# CHIP_tzatziffy_v8.net
KiCad netlist of a schematic drawn in EAGLE
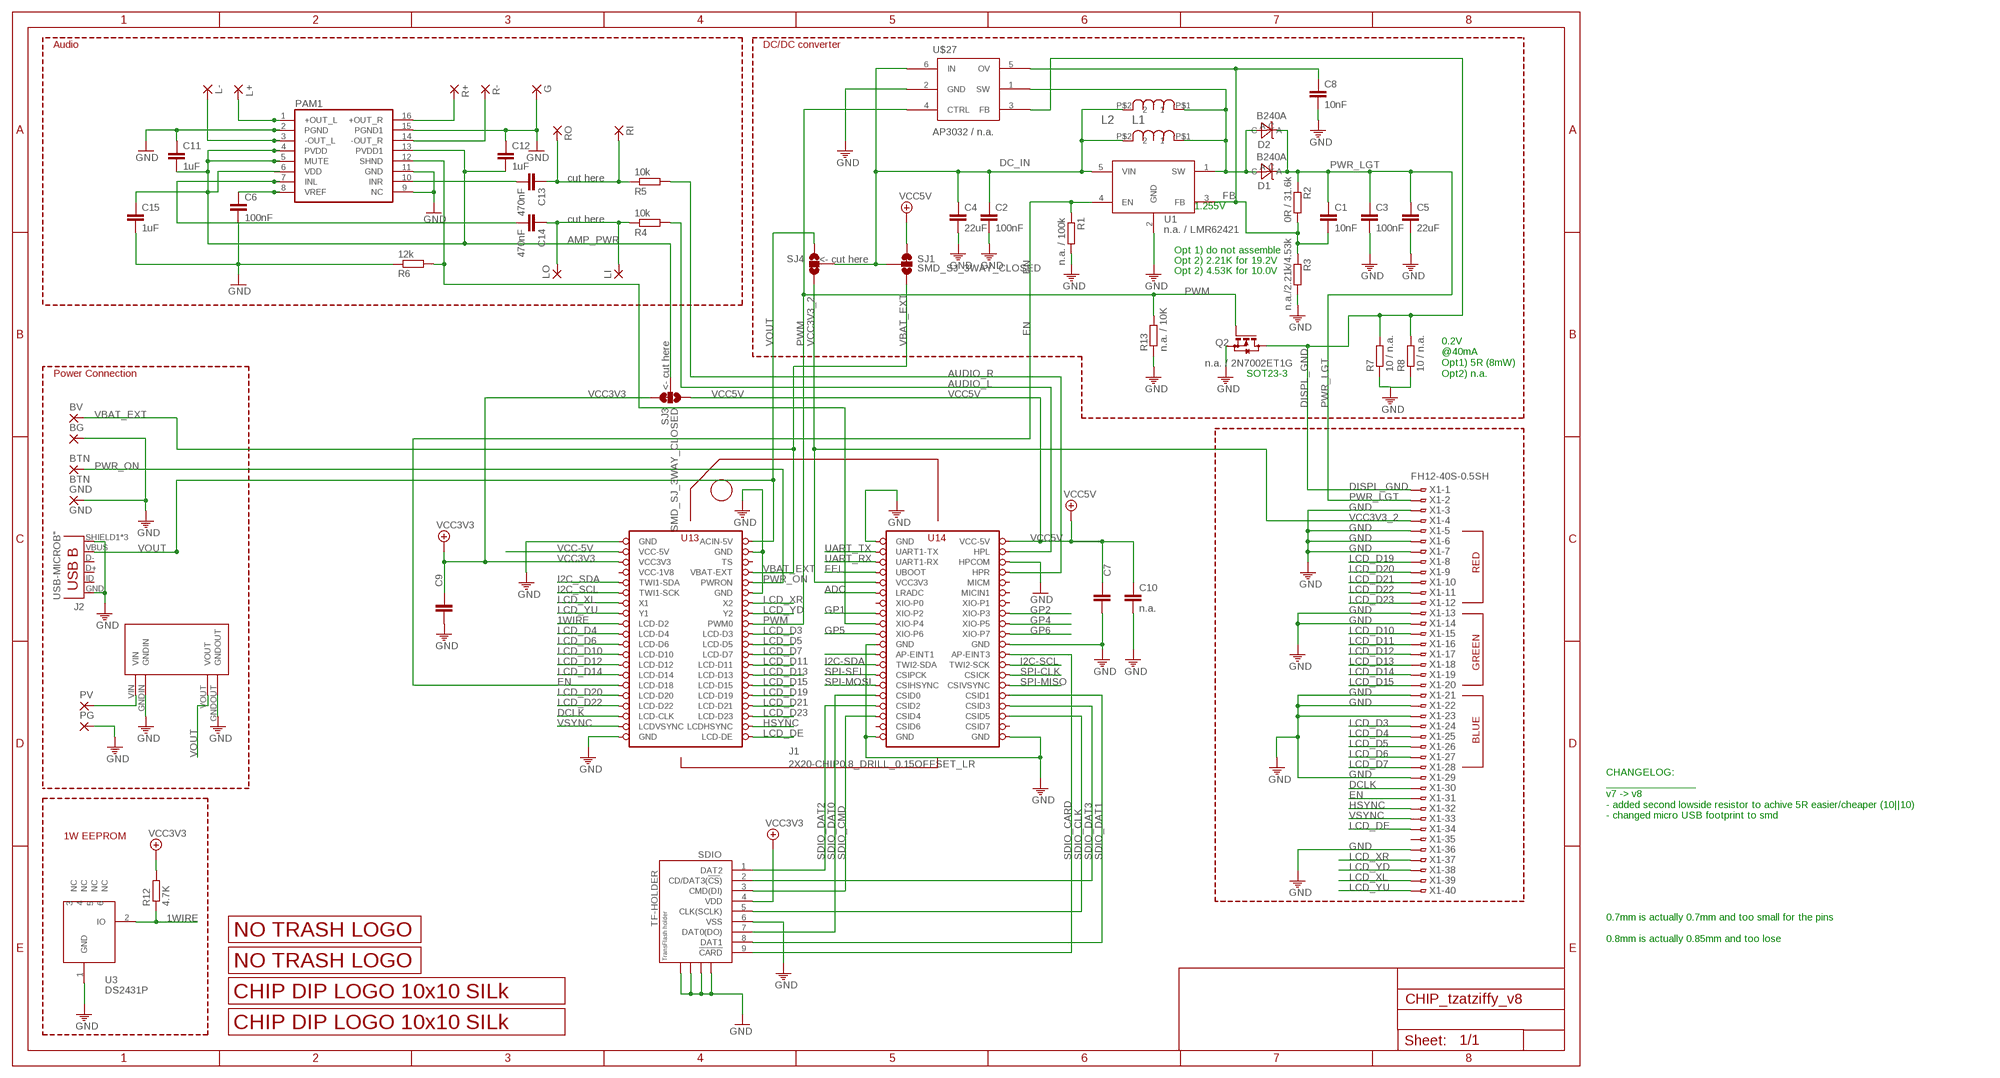
[diagram p0: schematic, sheet 1]

(export (version "E")
  (design (tool "Eeschema 10.0.6"))
  (components
    (comp (ref "BG")
      (value "1,6/0,8")
      (footprint "eagle-import:1,6_0,8")
      (libsource (lib "eagle-import") (part "1,6/0,8"))
    )
    (comp (ref "BTN")
      (value "BTN")
      (footprint "eagle-import:SMD1,27-2,54")
      (libsource (lib "eagle-import") (part "SMD2"))
    )
    (comp (ref "BV")
      (value "1,6/0,8")
      (footprint "eagle-import:1,6_0,8")
      (libsource (lib "eagle-import") (part "1,6/0,8"))
    )
    (comp (ref "C1")
      (value "10nF")
      (footprint "eagle-import:C0805")
      (libsource (lib "eagle-import") (part "C-EUC0805"))
    )
    (comp (ref "C2")
      (value "100nF")
      (footprint "eagle-import:C0805")
      (libsource (lib "eagle-import") (part "C-EUC0805"))
    )
    (comp (ref "C3")
      (value "100nF")
      (footprint "eagle-import:C0805")
      (libsource (lib "eagle-import") (part "C-EUC0805"))
    )
    (comp (ref "C4")
      (value "22uF")
      (footprint "eagle-import:C1206")
      (libsource (lib "eagle-import") (part "C-EUC1206"))
    )
    (comp (ref "C5")
      (value "22uF")
      (footprint "eagle-import:C1206")
      (libsource (lib "eagle-import") (part "C-EUC1206"))
    )
    (comp (ref "C6")
      (value "100nF")
      (footprint "eagle-import:C0805")
      (libsource (lib "eagle-import") (part "C-EUC0805"))
    )
    (comp (ref "C7")
      (value "n.a.")
      (footprint "eagle-import:C0805")
      (libsource (lib "eagle-import") (part "C-EUC0805"))
    )
    (comp (ref "C8")
      (value "10nF")
      (footprint "eagle-import:C0805")
      (libsource (lib "eagle-import") (part "C-EUC0805"))
    )
    (comp (ref "C9")
      (value "n.a.")
      (footprint "eagle-import:C0805")
      (libsource (lib "eagle-import") (part "C-EUC0805"))
    )
    (comp (ref "C10")
      (value "n.a.")
      (footprint "eagle-import:C0805")
      (libsource (lib "eagle-import") (part "C-EUC0805"))
    )
    (comp (ref "C11")
      (value "1uF")
      (footprint "eagle-import:C0805")
      (libsource (lib "eagle-import") (part "C-EUC0805"))
    )
    (comp (ref "C12")
      (value "1uF")
      (footprint "eagle-import:C0805")
      (libsource (lib "eagle-import") (part "C-EUC0805"))
    )
    (comp (ref "C13")
      (value "470nF")
      (footprint "eagle-import:C0805")
      (libsource (lib "eagle-import") (part "C-EUC0805"))
    )
    (comp (ref "C14")
      (value "470nF")
      (footprint "eagle-import:C0805")
      (libsource (lib "eagle-import") (part "C-EUC0805"))
    )
    (comp (ref "C15")
      (value "1uF")
      (footprint "eagle-import:C0805")
      (libsource (lib "eagle-import") (part "C-EUC0805"))
    )
    (comp (ref "D1")
      (value "B240A")
      (footprint "eagle-import:DO-214AC")
      (fields (field (name "MFG") "DIGIKEY") (field (name "VENDOR_PART_NUMBER") "B240A-13-F"))
      (libsource (lib "eagle-import") (part "DIODE_SCHTKY_B240"))
    )
    (comp (ref "D2")
      (value "B240A")
      (footprint "eagle-import:DO-214AC")
      (fields (field (name "MFG") "DIGIKEY") (field (name "VENDOR_PART_NUMBER") "B240A-13-F"))
      (libsource (lib "eagle-import") (part "DIODE_SCHTKY_B240"))
    )
    (comp (ref "G")
      (value "1,6/0,8")
      (footprint "eagle-import:1,6_0,8")
      (libsource (lib "eagle-import") (part "1,6/0,8"))
    )
    (comp (ref "GND")
      (value "GND")
      (footprint "eagle-import:SMD1,27-2,54")
      (libsource (lib "eagle-import") (part "SMD2"))
    )
    (comp (ref "J1")
      (value "2X20-CHIP0.8_DRILL_0.15OFFSET_LR")
      (footprint "eagle-import:2X20CHIP_0.15MM_OFFSET_TH_08")
      (libsource (lib "eagle-import") (part "2X20-CHIP0.8_DRILL_0.15OFFSET_LR"))
    )
    (comp (ref "J2")
      (value "USB-MICROB\"")
      (footprint "eagle-import:USB-B-MICRO-SMD_V03")
      (libsource (lib "eagle-import") (part "USB-MICROB{dblquote}"))
    )
    (comp (ref "L+")
      (value "1,6/0,8")
      (footprint "eagle-import:1,6_0,8")
      (libsource (lib "eagle-import") (part "1,6/0,8"))
    )
    (comp (ref "L-")
      (value "1,6/0,8")
      (footprint "eagle-import:1,6_0,8")
      (libsource (lib "eagle-import") (part "1,6/0,8"))
    )
    (comp (ref "L1")
      (value "SRN6045-100M")
      (footprint "eagle-import:SRN6045")
      (fields (field (name "MFG") "DIGIKEY"))
      (libsource (lib "eagle-import") (part "SRN6045-100M"))
    )
    (comp (ref "L2")
      (value "SRN6045-100M")
      (footprint "eagle-import:SRN6045")
      (fields (field (name "MFG") "DIGIKEY"))
      (libsource (lib "eagle-import") (part "SRN6045-100M"))
    )
    (comp (ref "LI")
      (value "1,6/0,8")
      (footprint "eagle-import:1,6_0,8")
      (libsource (lib "eagle-import") (part "1,6/0,8"))
    )
    (comp (ref "LO")
      (value "1,6/0,8")
      (footprint "eagle-import:1,6_0,8")
      (libsource (lib "eagle-import") (part "1,6/0,8"))
    )
    (comp (ref "PAM1")
      (value "PAM8403")
      (footprint "eagle-import:SOP-16")
      (libsource (lib "eagle-import") (part "PAM8403"))
    )
    (comp (ref "PG")
      (value "1,6/0,8")
      (footprint "eagle-import:1,6_0,8")
      (libsource (lib "eagle-import") (part "1,6/0,8"))
    )
    (comp (ref "PV")
      (value "1,6/0,8")
      (footprint "eagle-import:1,6_0,8")
      (libsource (lib "eagle-import") (part "1,6/0,8"))
    )
    (comp (ref "Q2")
      (value "n.a. / 2N7002ET1G")
      (footprint "eagle-import:SOT23")
      (libsource (lib "eagle-import") (part "BSS123"))
    )
    (comp (ref "R+")
      (value "1,6/0,8")
      (footprint "eagle-import:1,6_0,8")
      (libsource (lib "eagle-import") (part "1,6/0,8"))
    )
    (comp (ref "R-")
      (value "1,6/0,8")
      (footprint "eagle-import:1,6_0,8")
      (libsource (lib "eagle-import") (part "1,6/0,8"))
    )
    (comp (ref "R1")
      (value "n.a. / 100k")
      (footprint "eagle-import:M0805")
      (libsource (lib "eagle-import") (part "R-EU_M0805"))
    )
    (comp (ref "R2")
      (value "0R / 31.6k")
      (footprint "eagle-import:M0805")
      (libsource (lib "eagle-import") (part "R-EU_M0805"))
    )
    (comp (ref "R3")
      (value "n.a./2.21k/4.53k")
      (footprint "eagle-import:M0805")
      (libsource (lib "eagle-import") (part "R-EU_M0805"))
    )
    (comp (ref "R4")
      (value "10k")
      (footprint "eagle-import:R0805")
      (libsource (lib "eagle-import") (part "R-EU_R0805"))
    )
    (comp (ref "R5")
      (value "10k")
      (footprint "eagle-import:R0805")
      (libsource (lib "eagle-import") (part "R-EU_R0805"))
    )
    (comp (ref "R6")
      (value "12k")
      (footprint "eagle-import:R0805")
      (libsource (lib "eagle-import") (part "R-EU_R0805"))
    )
    (comp (ref "R7")
      (value "10 / n.a.")
      (footprint "eagle-import:M0805")
      (libsource (lib "eagle-import") (part "R-EU_M0805"))
    )
    (comp (ref "R8")
      (value "10 / n.a.")
      (footprint "eagle-import:M0805")
      (libsource (lib "eagle-import") (part "R-EU_M0805"))
    )
    (comp (ref "R12")
      (value "4.7K")
      (footprint "eagle-import:M0805")
      (libsource (lib "eagle-import") (part "R-EU_M0805"))
    )
    (comp (ref "R13")
      (value "n.a. / 10K")
      (footprint "eagle-import:M0805")
      (libsource (lib "eagle-import") (part "R-EU_M0805"))
    )
    (comp (ref "RI")
      (value "1,6/0,8")
      (footprint "eagle-import:1,6_0,8")
      (libsource (lib "eagle-import") (part "1,6/0,8"))
    )
    (comp (ref "RO")
      (value "1,6/0,8")
      (footprint "eagle-import:1,6_0,8")
      (libsource (lib "eagle-import") (part "1,6/0,8"))
    )
    (comp (ref "SDIO")
      (value "TF-HOLDER")
      (footprint "eagle-import:TF-PULL")
      (libsource (lib "eagle-import") (part "TF-HOLDER"))
    )
    (comp (ref "SJ1")
      (value "SMD_SJ_3WAY_CLOSED")
      (footprint "eagle-import:SMD_SJ_3WAY_CLOSED")
      (libsource (lib "eagle-import") (part "SMD_SJ_3WAY_CLOSED"))
    )
    (comp (ref "SJ3")
      (value "SMD_SJ_3WAY_CLOSED")
      (footprint "eagle-import:SMD_SJ_3WAY_CLOSED")
      (libsource (lib "eagle-import") (part "SMD_SJ_3WAY_CLOSED"))
    )
    (comp (ref "SJ4")
      (value "SMD_SJ_3WAY_OPENT")
      (footprint "eagle-import:SMD_SJ_3WAY_OPEN")
      (libsource (lib "eagle-import") (part "SMD_SJ_3WAY_OPENT"))
    )
    (comp (ref "U$2")
      (value "LOGO_10X10_SILK")
      (footprint "eagle-import:LOGO2_10X10_SILK")
      (libsource (lib "eagle-import") (part "LOGO_10X10_SILK"))
    )
    (comp (ref "U$3")
      (value "LOGO_NO_TRASHROHS")
      (footprint "eagle-import:LOGO_ROHS_SYM")
      (libsource (lib "eagle-import") (part "LOGO_NO_TRASHROHS"))
    )
    (comp (ref "U$4")
      (value "LOGO_NO_TRASHNO_TRASH")
      (footprint "eagle-import:LOGO_ROHS_NO_TRASH")
      (libsource (lib "eagle-import") (part "LOGO_NO_TRASHNO_TRASH"))
    )
    (comp (ref "U$5")
      (value "LOGO_10X10_SILK")
      (footprint "eagle-import:LOGO2_10X10_SILK")
      (libsource (lib "eagle-import") (part "LOGO_10X10_SILK"))
    )
    (comp (ref "U$10")
      (value "MP1584EN_FRAMELESS")
      (footprint "eagle-import:MP1584EN_FRAMELESS")
      (libsource (lib "eagle-import") (part "MP1584EN_FRAMELESS"))
    )
    (comp (ref "U$27")
      (value "AP3032 / n.a.")
      (footprint "eagle-import:SOT23-6")
      (libsource (lib "eagle-import") (part "AP3032"))
    )
    (comp (ref "U1")
      (value "n.a. / LMR62421")
      (footprint "eagle-import:SOT23-5")
      (fields (field (name "MFG") "DIGIKEY") (field (name "VENDOR_PART_NUMBER") "LMR62421XMFE/NOPB"))
      (libsource (lib "eagle-import") (part "LMR62421"))
    )
    (comp (ref "U3")
      (value "DS2431P")
      (footprint "eagle-import:TSOC6")
      (fields (field (name "MFG") "DIGIKEY") (field (name "VENDOR_PART_NUMBER") "DS2431P+T&R"))
      (libsource (lib "eagle-import") (part "DS2431P"))
    )
    (comp (ref "X1")
      (value "FH12-40S-0.5SH")
      (footprint "eagle-import:FH12-40S-0.5SH")
      (fields (field (name "MFG") "DIGIKEY") (field (name "VENDOR_PART_NUMBER") "FH12-40S-0.5SH(55)"))
      (libsource (lib "eagle-import") (part "FH12-40S-0.5SH"))
    )
  )
  (nets
    (net (code "1") (name "/1WIRE") (class "Default")
      (node (ref "J1") (pin "LCD-D2") (pinfunction "LCD-D2_LCD-D2") (pintype "passive"))
      (node (ref "R12") (pin "1") (pinfunction "1_1") (pintype "passive"))
      (node (ref "U3") (pin "2") (pinfunction "IO_2") (pintype "bidirectional"))
    )
    (net (code "2") (name "/ADC") (class "Default")
      (node (ref "J1") (pin "LRADC") (pinfunction "LRADC_LRADC") (pintype "passive"))
    )
    (net (code "3") (name "/AMP_PWR") (class "Default")
      (node (ref "C11") (pin "2") (pinfunction "2_2") (pintype "passive"))
      (node (ref "C12") (pin "2") (pinfunction "2_2") (pintype "passive"))
      (node (ref "C15") (pin "1") (pinfunction "1_1") (pintype "passive"))
      (node (ref "PAM1") (pin "13") (pinfunction "PVDD1_13") (pintype "output"))
      (node (ref "PAM1") (pin "4") (pinfunction "PVDD_4") (pintype "input"))
      (node (ref "PAM1") (pin "5") (pinfunction "MUTE_5") (pintype "input"))
      (node (ref "PAM1") (pin "6") (pinfunction "VDD_6") (pintype "input"))
      (node (ref "SJ3") (pin "2") (pinfunction "2_2") (pintype "passive"))
    )
    (net (code "4") (name "/AUDIO_L") (class "Default")
      (node (ref "J1") (pin "HPL") (pinfunction "HPL_HPL") (pintype "passive"))
      (node (ref "R4") (pin "2") (pinfunction "2_2") (pintype "passive"))
    )
    (net (code "5") (name "/AUDIO_R") (class "Default")
      (node (ref "J1") (pin "HPR") (pinfunction "HPR_HPR") (pintype "passive"))
      (node (ref "R5") (pin "2") (pinfunction "2_2") (pintype "passive"))
    )
    (net (code "6") (name "/DCLK") (class "Default")
      (node (ref "J1") (pin "LCD-CLK") (pinfunction "LCD-CLK_LCD-CLK") (pintype "passive"))
      (node (ref "X1") (pin "30") (pinfunction "1_30") (pintype "passive"))
    )
    (net (code "7") (name "/DC_IN") (class "Default")
      (node (ref "C2") (pin "1") (pinfunction "1_1") (pintype "passive"))
      (node (ref "C4") (pin "1") (pinfunction "1_1") (pintype "passive"))
      (node (ref "L1") (pin "P$2") (pinfunction "2_P$2") (pintype "passive"))
      (node (ref "L2") (pin "P$2") (pinfunction "2_P$2") (pintype "passive"))
      (node (ref "SJ1") (pin "2") (pinfunction "2_2") (pintype "passive"))
      (node (ref "SJ4") (pin "2") (pinfunction "2_2") (pintype "passive"))
      (node (ref "U$27") (pin "6") (pinfunction "IN_6") (pintype "power_in"))
      (node (ref "U1") (pin "5") (pinfunction "VIN_5") (pintype "bidirectional"))
    )
    (net (code "8") (name "/DISPL_GND") (class "Default")
      (node (ref "Q2") (pin "3") (pinfunction "D_3") (pintype "passive"))
      (node (ref "R7") (pin "2") (pinfunction "2_2") (pintype "passive"))
      (node (ref "R8") (pin "2") (pinfunction "2_2") (pintype "passive"))
      (node (ref "U$27") (pin "3") (pinfunction "FB_3") (pintype "passive"))
      (node (ref "X1") (pin "1") (pinfunction "1_1") (pintype "passive"))
    )
    (net (code "9") (name "/EN") (class "Default")
      (node (ref "J1") (pin "LCD-D18") (pinfunction "LCD-D18_LCD-D18") (pintype "passive"))
      (node (ref "R1") (pin "1") (pinfunction "1_1") (pintype "passive"))
      (node (ref "U1") (pin "4") (pinfunction "EN_4") (pintype "bidirectional"))
      (node (ref "X1") (pin "31") (pinfunction "1_31") (pintype "passive"))
    )
    (net (code "10") (name "/FB") (class "Default")
      (node (ref "C1") (pin "2") (pinfunction "2_2") (pintype "passive"))
      (node (ref "C8") (pin "1") (pinfunction "1_1") (pintype "passive"))
      (node (ref "R2") (pin "2") (pinfunction "2_2") (pintype "passive"))
      (node (ref "R3") (pin "1") (pinfunction "1_1") (pintype "passive"))
      (node (ref "U$27") (pin "5") (pinfunction "OV_5") (pintype "power_in"))
      (node (ref "U1") (pin "3") (pinfunction "FB_3") (pintype "bidirectional"))
    )
    (net (code "11") (name "/FEL") (class "Default")
      (node (ref "J1") (pin "FEL") (pinfunction "UBOOT_FEL") (pintype "passive"))
    )
    (net (code "12") (name "/GP1") (class "Default")
      (node (ref "J1") (pin "XIO-P2") (pinfunction "XIO-P2_XIO-P2") (pintype "passive"))
    )
    (net (code "13") (name "/GP2") (class "Default")
      (node (ref "J1") (pin "XIO-P3") (pinfunction "XIO-P3_XIO-P3") (pintype "passive"))
    )
    (net (code "14") (name "/GP4") (class "Default")
      (node (ref "J1") (pin "XIO-P5") (pinfunction "XIO-P5_XIO-P5") (pintype "passive"))
    )
    (net (code "15") (name "/GP5") (class "Default")
      (node (ref "J1") (pin "XIO-P6") (pinfunction "XIO-P6_XIO-P6") (pintype "passive"))
    )
    (net (code "16") (name "/GP6") (class "Default")
      (node (ref "J1") (pin "XIO-P7") (pinfunction "XIO-P7_XIO-P7") (pintype "passive"))
    )
    (net (code "17") (name "/HSYNC") (class "Default")
      (node (ref "J1") (pin "LCD-HSYNC") (pinfunction "LCDHSYNC_LCD-HSYNC") (pintype "passive"))
      (node (ref "X1") (pin "32") (pinfunction "1_32") (pintype "passive"))
    )
    (net (code "18") (name "/I2C-SCL") (class "Default")
      (node (ref "J1") (pin "TWI2-SCK") (pinfunction "TWI2-SCK_TWI2-SCK") (pintype "passive"))
    )
    (net (code "19") (name "/I2C-SDA") (class "Default")
      (node (ref "J1") (pin "TWI2-SDA") (pinfunction "TWI2-SDA_TWI2-SDA") (pintype "passive"))
    )
    (net (code "20") (name "/I2C_SCL") (class "Default")
      (node (ref "J1") (pin "TWI1-SCK") (pinfunction "TWI1-SCK_TWI1-SCK") (pintype "passive"))
    )
    (net (code "21") (name "/I2C_SDA") (class "Default")
      (node (ref "J1") (pin "TWI1-SDA") (pinfunction "TWI1-SDA_TWI1-SDA") (pintype "passive"))
    )
    (net (code "22") (name "/LCD_D3") (class "Default")
      (node (ref "J1") (pin "LCD-D3") (pinfunction "LCD-D3_LCD-D3") (pintype "passive"))
      (node (ref "X1") (pin "24") (pinfunction "1_24") (pintype "passive"))
    )
    (net (code "23") (name "/LCD_D4") (class "Default")
      (node (ref "J1") (pin "LCD-D4") (pinfunction "LCD-D4_LCD-D4") (pintype "passive"))
      (node (ref "X1") (pin "25") (pinfunction "1_25") (pintype "passive"))
    )
    (net (code "24") (name "/LCD_D5") (class "Default")
      (node (ref "J1") (pin "LCD-D5") (pinfunction "LCD-D5_LCD-D5") (pintype "passive"))
      (node (ref "X1") (pin "26") (pinfunction "1_26") (pintype "passive"))
    )
    (net (code "25") (name "/LCD_D6") (class "Default")
      (node (ref "J1") (pin "LCD-D6") (pinfunction "LCD-D6_LCD-D6") (pintype "passive"))
      (node (ref "X1") (pin "27") (pinfunction "1_27") (pintype "passive"))
    )
    (net (code "26") (name "/LCD_D7") (class "Default")
      (node (ref "J1") (pin "LCD-D7") (pinfunction "LCD-D7_LCD-D7") (pintype "passive"))
      (node (ref "X1") (pin "28") (pinfunction "1_28") (pintype "passive"))
    )
    (net (code "27") (name "/LCD_D10") (class "Default")
      (node (ref "J1") (pin "LCD-D10") (pinfunction "LCD-D10_LCD-D10") (pintype "passive"))
      (node (ref "X1") (pin "15") (pinfunction "1_15") (pintype "passive"))
    )
    (net (code "28") (name "/LCD_D11") (class "Default")
      (node (ref "J1") (pin "LCD-D11") (pinfunction "LCD-D11_LCD-D11") (pintype "passive"))
      (node (ref "X1") (pin "16") (pinfunction "1_16") (pintype "passive"))
    )
    (net (code "29") (name "/LCD_D12") (class "Default")
      (node (ref "J1") (pin "LCD-D12") (pinfunction "LCD-D12_LCD-D12") (pintype "passive"))
      (node (ref "X1") (pin "17") (pinfunction "1_17") (pintype "passive"))
    )
    (net (code "30") (name "/LCD_D13") (class "Default")
      (node (ref "J1") (pin "LCD-D13") (pinfunction "LCD-D13_LCD-D13") (pintype "passive"))
      (node (ref "X1") (pin "18") (pinfunction "1_18") (pintype "passive"))
    )
    (net (code "31") (name "/LCD_D14") (class "Default")
      (node (ref "J1") (pin "LCD-D14") (pinfunction "LCD-D14_LCD-D14") (pintype "passive"))
      (node (ref "X1") (pin "19") (pinfunction "1_19") (pintype "passive"))
    )
    (net (code "32") (name "/LCD_D15") (class "Default")
      (node (ref "J1") (pin "LCD-D15") (pinfunction "LCD-D15_LCD-D15") (pintype "passive"))
      (node (ref "X1") (pin "20") (pinfunction "1_20") (pintype "passive"))
    )
    (net (code "33") (name "/LCD_D19") (class "Default")
      (node (ref "J1") (pin "LCD-D19") (pinfunction "LCD-D19_LCD-D19") (pintype "passive"))
      (node (ref "X1") (pin "8") (pinfunction "1_8") (pintype "passive"))
    )
    (net (code "34") (name "/LCD_D20") (class "Default")
      (node (ref "J1") (pin "LCD-D20") (pinfunction "LCD-D20_LCD-D20") (pintype "passive"))
      (node (ref "X1") (pin "9") (pinfunction "1_9") (pintype "passive"))
    )
    (net (code "35") (name "/LCD_D21") (class "Default")
      (node (ref "J1") (pin "LCD-D21") (pinfunction "LCD-D21_LCD-D21") (pintype "passive"))
      (node (ref "X1") (pin "10") (pinfunction "1_10") (pintype "passive"))
    )
    (net (code "36") (name "/LCD_D22") (class "Default")
      (node (ref "J1") (pin "LCD-D22") (pinfunction "LCD-D22_LCD-D22") (pintype "passive"))
      (node (ref "X1") (pin "11") (pinfunction "1_11") (pintype "passive"))
    )
    (net (code "37") (name "/LCD_D23") (class "Default")
      (node (ref "J1") (pin "LCD-D23") (pinfunction "LCD-D23_LCD-D23") (pintype "passive"))
      (node (ref "X1") (pin "12") (pinfunction "1_12") (pintype "passive"))
    )
    (net (code "38") (name "/LCD_DE") (class "Default")
      (node (ref "J1") (pin "LCD-DE") (pinfunction "LCD-DE_LCD-DE") (pintype "passive"))
      (node (ref "X1") (pin "34") (pinfunction "1_34") (pintype "passive"))
    )
    (net (code "39") (name "/LCD_XL") (class "Default")
      (node (ref "J1") (pin "X1") (pinfunction "X1_X1") (pintype "passive"))
      (node (ref "X1") (pin "39") (pinfunction "1_39") (pintype "passive"))
    )
    (net (code "40") (name "/LCD_XR") (class "Default")
      (node (ref "J1") (pin "X2") (pinfunction "X2_X2") (pintype "passive"))
      (node (ref "X1") (pin "37") (pinfunction "1_37") (pintype "passive"))
    )
    (net (code "41") (name "/LCD_YD") (class "Default")
      (node (ref "J1") (pin "Y2") (pinfunction "Y2_Y2") (pintype "passive"))
      (node (ref "X1") (pin "38") (pinfunction "1_38") (pintype "passive"))
    )
    (net (code "42") (name "/LCD_YU") (class "Default")
      (node (ref "J1") (pin "Y1") (pinfunction "Y1_Y1") (pintype "passive"))
      (node (ref "X1") (pin "40") (pinfunction "1_40") (pintype "passive"))
    )
    (net (code "43") (name "/PWM") (class "Default")
      (node (ref "J1") (pin "PWM0") (pinfunction "PWM0_PWM0") (pintype "passive"))
      (node (ref "Q2") (pin "1") (pinfunction "G_1") (pintype "passive"))
      (node (ref "R13") (pin "2") (pinfunction "2_2") (pintype "passive"))
      (node (ref "U$27") (pin "4") (pinfunction "CTRL_4") (pintype "input"))
    )
    (net (code "44") (name "/PWR_LGT") (class "Default")
      (node (ref "C1") (pin "1") (pinfunction "1_1") (pintype "passive"))
      (node (ref "C3") (pin "1") (pinfunction "1_1") (pintype "passive"))
      (node (ref "C5") (pin "1") (pinfunction "1_1") (pintype "passive"))
      (node (ref "D1") (pin "C") (pinfunction "C_C") (pintype "bidirectional"))
      (node (ref "D2") (pin "C") (pinfunction "C_C") (pintype "bidirectional"))
      (node (ref "R2") (pin "1") (pinfunction "1_1") (pintype "passive"))
      (node (ref "X1") (pin "2") (pinfunction "1_2") (pintype "passive"))
    )
    (net (code "45") (name "/PWR_ON") (class "Default")
      (node (ref "BTN") (pin "1") (pinfunction "P_1") (pintype "passive"))
      (node (ref "J1") (pin "PWRON") (pinfunction "PWRON_PWRON") (pintype "passive"))
    )
    (net (code "46") (name "/SDIO_CARD") (class "Default")
      (node (ref "J1") (pin "AP-EINT3") (pinfunction "AP-EINT3_AP-EINT3") (pintype "passive"))
      (node (ref "SDIO") (pin "9") (pinfunction "~{CARD}_9") (pintype "passive"))
    )
    (net (code "47") (name "/SDIO_CLK") (class "Default")
      (node (ref "J1") (pin "CSID5") (pinfunction "CSID5_CSID5") (pintype "passive"))
      (node (ref "SDIO") (pin "5") (pinfunction "CLK(SCLK)_5") (pintype "input"))
    )
    (net (code "48") (name "/SDIO_CMD") (class "Default")
      (node (ref "J1") (pin "CSID4") (pinfunction "CSID4_CSID4") (pintype "passive"))
      (node (ref "SDIO") (pin "3") (pinfunction "CMD(DI)_3") (pintype "bidirectional"))
    )
    (net (code "49") (name "/SDIO_DAT0") (class "Default")
      (node (ref "J1") (pin "CSID0") (pinfunction "CSID0_CSID0") (pintype "passive"))
      (node (ref "SDIO") (pin "7") (pinfunction "DAT0(DO)_7") (pintype "bidirectional"))
    )
    (net (code "50") (name "/SDIO_DAT1") (class "Default")
      (node (ref "J1") (pin "CSID1") (pinfunction "CSID1_CSID1") (pintype "passive"))
      (node (ref "SDIO") (pin "8") (pinfunction "DAT1_8") (pintype "bidirectional"))
    )
    (net (code "51") (name "/SDIO_DAT2") (class "Default")
      (node (ref "J1") (pin "CSID2") (pinfunction "CSID2_CSID2") (pintype "passive"))
      (node (ref "SDIO") (pin "1") (pinfunction "DAT2_1") (pintype "bidirectional"))
    )
    (net (code "52") (name "/SDIO_DAT3") (class "Default")
      (node (ref "J1") (pin "CSID3") (pinfunction "CSID3_CSID3") (pintype "passive"))
      (node (ref "SDIO") (pin "2") (pinfunction "CD/DAT3(~{CS})_2") (pintype "bidirectional"))
    )
    (net (code "53") (name "/SPI-CLK") (class "Default")
      (node (ref "J1") (pin "CSICK") (pinfunction "CSICK_CSICK") (pintype "passive"))
    )
    (net (code "54") (name "/SPI-MISO") (class "Default")
      (node (ref "J1") (pin "CSIVSYNC") (pinfunction "CSIVSYNC_CSIVSYNC") (pintype "passive"))
    )
    (net (code "55") (name "/SPI-MOSI") (class "Default")
      (node (ref "J1") (pin "CSIHSYNC") (pinfunction "CSIHSYNC_CSIHSYNC") (pintype "passive"))
    )
    (net (code "56") (name "/SPI-SEL") (class "Default")
      (node (ref "J1") (pin "CSIPCK") (pinfunction "CSIPCK_CSIPCK") (pintype "passive"))
    )
    (net (code "57") (name "/UART_RX") (class "Default")
      (node (ref "J1") (pin "UART1-RX") (pinfunction "UART1-RX_UART1-RX") (pintype "passive"))
    )
    (net (code "58") (name "/UART_TX") (class "Default")
      (node (ref "J1") (pin "UART1-TX") (pinfunction "UART1-TX_UART1-TX") (pintype "passive"))
    )
    (net (code "59") (name "/VBAT_EXT") (class "Default")
      (node (ref "BV") (pin "1") (pinfunction "P_1") (pintype "passive"))
      (node (ref "J1") (pin "BAT") (pinfunction "VBAT-EXT_BAT") (pintype "passive"))
      (node (ref "SJ1") (pin "3") (pinfunction "3_3") (pintype "passive"))
    )
    (net (code "60") (name "/VCC-1V8") (class "Default")
      (node (ref "J1") (pin "VCC1V8") (pinfunction "VCC-1V8_VCC1V8") (pintype "power_in"))
    )
    (net (code "61") (name "/VCC-5V") (class "Default")
      (node (ref "J1") (pin "VCC5V@0") (pinfunction "VCC-5V_VCC5V@0") (pintype "power_in"))
    )
    (net (code "62") (name "/VCC3V3_2") (class "Default")
      (node (ref "J1") (pin "VCC3V3@1") (pinfunction "VCC3V3_VCC3V3@1") (pintype "power_in"))
      (node (ref "SJ4") (pin "3") (pinfunction "3_3") (pintype "passive"))
      (node (ref "X1") (pin "4") (pinfunction "1_4") (pintype "passive"))
    )
    (net (code "63") (name "/VOUT") (class "Default")
      (node (ref "J1") (pin "CHG-IN") (pinfunction "ACIN-5V_CHG-IN") (pintype "passive"))
      (node (ref "J2") (pin "VBUS") (pinfunction "VBUS_VBUS") (pintype "bidirectional"))
      (node (ref "SJ4") (pin "1") (pinfunction "1_1") (pintype "passive"))
      (node (ref "U$10") (pin "VOUT") (pinfunction "VOUT_VOUT") (pintype "power_in"))
    )
    (net (code "64") (name "/VSYNC") (class "Default")
      (node (ref "J1") (pin "LCD-VSYNC") (pinfunction "LCDVSYNC_LCD-VSYNC") (pintype "passive"))
      (node (ref "X1") (pin "33") (pinfunction "1_33") (pintype "passive"))
    )
    (net (code "65") (name "GND") (class "Default")
      (node (ref "BG") (pin "1") (pinfunction "P_1") (pintype "passive"))
      (node (ref "C10") (pin "2") (pinfunction "2_2") (pintype "passive"))
      (node (ref "C11") (pin "1") (pinfunction "1_1") (pintype "passive"))
      (node (ref "C12") (pin "1") (pinfunction "1_1") (pintype "passive"))
      (node (ref "C15") (pin "2") (pinfunction "2_2") (pintype "passive"))
      (node (ref "C2") (pin "2") (pinfunction "2_2") (pintype "passive"))
      (node (ref "C3") (pin "2") (pinfunction "2_2") (pintype "passive"))
      (node (ref "C4") (pin "2") (pinfunction "2_2") (pintype "passive"))
      (node (ref "C5") (pin "2") (pinfunction "2_2") (pintype "passive"))
      (node (ref "C6") (pin "2") (pinfunction "2_2") (pintype "passive"))
      (node (ref "C7") (pin "2") (pinfunction "2_2") (pintype "passive"))
      (node (ref "C8") (pin "2") (pinfunction "2_2") (pintype "passive"))
      (node (ref "C9") (pin "2") (pinfunction "2_2") (pintype "passive"))
      (node (ref "G") (pin "1") (pinfunction "P_1") (pintype "passive"))
      (node (ref "GND") (pin "1") (pinfunction "P_1") (pintype "passive"))
      (node (ref "J1") (pin "GND@1") (pinfunction "GND_GND@1") (pintype "power_in"))
      (node (ref "J1") (pin "GND@10") (pinfunction "GND_GND@10") (pintype "power_in"))
      (node (ref "J1") (pin "GND@2") (pinfunction "GND_GND@2") (pintype "power_in"))
      (node (ref "J1") (pin "GND@3") (pinfunction "GND_GND@3") (pintype "power_in"))
      (node (ref "J1") (pin "GND@4") (pinfunction "GND_GND@4") (pintype "power_in"))
      (node (ref "J1") (pin "GND@5") (pinfunction "GND_GND@5") (pintype "power_in"))
      (node (ref "J1") (pin "GND@6") (pinfunction "GND_GND@6") (pintype "power_in"))
      (node (ref "J1") (pin "GND@7") (pinfunction "GND_GND@7") (pintype "power_in"))
      (node (ref "J1") (pin "GND@8") (pinfunction "GND_GND@8") (pintype "power_in"))
      (node (ref "J1") (pin "HPCOM") (pinfunction "HPCOM_HPCOM") (pintype "passive"))
      (node (ref "J2") (pin "GND") (pinfunction "GND_GND") (pintype "bidirectional"))
      (node (ref "J2") (pin "SHIELD1") (pinfunction "SHIELD_SHIELD1") (pintype "bidirectional"))
      (node (ref "J2") (pin "SHIELD2") (pinfunction "SHIELD_SHIELD2") (pintype "bidirectional"))
      (node (ref "J2") (pin "SHIELD3") (pinfunction "SHIELD_SHIELD3") (pintype "bidirectional"))
      (node (ref "PAM1") (pin "11") (pinfunction "GND_11") (pintype "output"))
      (node (ref "PAM1") (pin "15") (pinfunction "PGND1_15") (pintype "output"))
      (node (ref "PAM1") (pin "2") (pinfunction "PGND_2") (pintype "input"))
      (node (ref "PAM1") (pin "9") (pinfunction "NC_9") (pintype "output"))
      (node (ref "PG") (pin "1") (pinfunction "P_1") (pintype "passive"))
      (node (ref "Q2") (pin "2") (pinfunction "S_2") (pintype "passive"))
      (node (ref "R1") (pin "2") (pinfunction "2_2") (pintype "passive"))
      (node (ref "R13") (pin "1") (pinfunction "1_1") (pintype "passive"))
      (node (ref "R3") (pin "2") (pinfunction "2_2") (pintype "passive"))
      (node (ref "R6") (pin "1") (pinfunction "1_1") (pintype "passive"))
      (node (ref "R7") (pin "1") (pinfunction "1_1") (pintype "passive"))
      (node (ref "R8") (pin "1") (pinfunction "1_1") (pintype "passive"))
      (node (ref "SDIO") (pin "6") (pinfunction "VSS_6") (pintype "power_in"))
      (node (ref "SDIO") (pin "S1") (pinfunction "S1_S1") (pintype "passive"))
      (node (ref "SDIO") (pin "S2") (pinfunction "S2_S2") (pintype "passive"))
      (node (ref "SDIO") (pin "S3") (pinfunction "S3_S3") (pintype "passive"))
      (node (ref "SDIO") (pin "S4") (pinfunction "S4_S4") (pintype "passive"))
      (node (ref "U$10") (pin "GNDIN") (pinfunction "GNDIN_GNDIN") (pintype "power_in"))
      (node (ref "U$10") (pin "GNDOUT") (pinfunction "GNDOUT_GNDOUT") (pintype "power_in"))
      (node (ref "U$27") (pin "2") (pinfunction "GND_2") (pintype "power_in"))
      (node (ref "U1") (pin "2") (pinfunction "GND_2") (pintype "bidirectional"))
      (node (ref "U3") (pin "1") (pinfunction "GND_1") (pintype "bidirectional"))
      (node (ref "X1") (pin "13") (pinfunction "1_13") (pintype "passive"))
      (node (ref "X1") (pin "14") (pinfunction "1_14") (pintype "passive"))
      (node (ref "X1") (pin "21") (pinfunction "1_21") (pintype "passive"))
      (node (ref "X1") (pin "22") (pinfunction "1_22") (pintype "passive"))
      (node (ref "X1") (pin "23") (pinfunction "1_23") (pintype "passive"))
      (node (ref "X1") (pin "29") (pinfunction "1_29") (pintype "passive"))
      (node (ref "X1") (pin "3") (pinfunction "1_3") (pintype "passive"))
      (node (ref "X1") (pin "36") (pinfunction "1_36") (pintype "passive"))
      (node (ref "X1") (pin "5") (pinfunction "1_5") (pintype "passive"))
      (node (ref "X1") (pin "6") (pinfunction "1_6") (pintype "passive"))
      (node (ref "X1") (pin "7") (pinfunction "1_7") (pintype "passive"))
    )
    (net (code "66") (name "Net-(L+-P)") (class "Default")
      (node (ref "L+") (pin "1") (pinfunction "P_1") (pintype "passive"))
      (node (ref "PAM1") (pin "1") (pinfunction "+OUT_L_1") (pintype "input"))
    )
    (net (code "67") (name "Net-(L--P)") (class "Default")
      (node (ref "L-") (pin "1") (pinfunction "P_1") (pintype "passive"))
      (node (ref "PAM1") (pin "3") (pinfunction "-OUT_L_3") (pintype "input"))
    )
    (net (code "68") (name "Net-(L1-1)") (class "Default")
      (node (ref "D1") (pin "A") (pinfunction "A_A") (pintype "bidirectional"))
      (node (ref "D2") (pin "A") (pinfunction "A_A") (pintype "bidirectional"))
      (node (ref "L1") (pin "P$1") (pinfunction "1_P$1") (pintype "passive"))
      (node (ref "L2") (pin "P$1") (pinfunction "1_P$1") (pintype "passive"))
      (node (ref "U$27") (pin "1") (pinfunction "SW_1") (pintype "power_in"))
      (node (ref "U1") (pin "1") (pinfunction "SW_1") (pintype "bidirectional"))
    )
    (net (code "69") (name "Net-(LI-P)") (class "Default")
      (node (ref "C14") (pin "1") (pinfunction "1_1") (pintype "passive"))
      (node (ref "LI") (pin "1") (pinfunction "P_1") (pintype "passive"))
      (node (ref "LO") (pin "1") (pinfunction "P_1") (pintype "passive"))
      (node (ref "R4") (pin "1") (pinfunction "1_1") (pintype "passive"))
    )
    (net (code "70") (name "Net-(PAM1-+OUT_R)") (class "Default")
      (node (ref "PAM1") (pin "16") (pinfunction "+OUT_R_16") (pintype "output"))
      (node (ref "R+") (pin "1") (pinfunction "P_1") (pintype "passive"))
    )
    (net (code "71") (name "Net-(PAM1--OUT_R)") (class "Default")
      (node (ref "PAM1") (pin "14") (pinfunction "-OUT_R_14") (pintype "output"))
      (node (ref "R-") (pin "1") (pinfunction "P_1") (pintype "passive"))
    )
    (net (code "72") (name "Net-(PAM1-INL)") (class "Default")
      (node (ref "C14") (pin "2") (pinfunction "2_2") (pintype "passive"))
      (node (ref "PAM1") (pin "7") (pinfunction "INL_7") (pintype "input"))
    )
    (net (code "73") (name "Net-(PAM1-INR)") (class "Default")
      (node (ref "C13") (pin "2") (pinfunction "2_2") (pintype "passive"))
      (node (ref "PAM1") (pin "10") (pinfunction "INR_10") (pintype "output"))
    )
    (net (code "74") (name "Net-(PAM1-SHND)") (class "Default")
      (node (ref "J1") (pin "XIO-P4") (pinfunction "XIO-P4_XIO-P4") (pintype "passive"))
      (node (ref "PAM1") (pin "12") (pinfunction "SHND_12") (pintype "output"))
      (node (ref "R6") (pin "2") (pinfunction "2_2") (pintype "passive"))
    )
    (net (code "75") (name "Net-(PAM1-VREF)") (class "Default")
      (node (ref "C6") (pin "1") (pinfunction "1_1") (pintype "passive"))
      (node (ref "PAM1") (pin "8") (pinfunction "VREF_8") (pintype "input"))
    )
    (net (code "76") (name "Net-(PV-P)") (class "Default")
      (node (ref "PV") (pin "1") (pinfunction "P_1") (pintype "passive"))
      (node (ref "U$10") (pin "VIN") (pinfunction "VIN_VIN") (pintype "power_in"))
    )
    (net (code "77") (name "Net-(RI-P)") (class "Default")
      (node (ref "C13") (pin "1") (pinfunction "1_1") (pintype "passive"))
      (node (ref "R5") (pin "1") (pinfunction "1_1") (pintype "passive"))
      (node (ref "RI") (pin "1") (pinfunction "P_1") (pintype "passive"))
      (node (ref "RO") (pin "1") (pinfunction "P_1") (pintype "passive"))
    )
    (net (code "78") (name "VCC3V3") (class "Default")
      (node (ref "C9") (pin "1") (pinfunction "1_1") (pintype "passive"))
      (node (ref "J1") (pin "VCC3V3") (pinfunction "VCC3V3_VCC3V3") (pintype "power_in"))
      (node (ref "R12") (pin "2") (pinfunction "2_2") (pintype "passive"))
      (node (ref "SDIO") (pin "4") (pinfunction "VDD_4") (pintype "power_in"))
      (node (ref "SJ3") (pin "1") (pinfunction "1_1") (pintype "passive"))
    )
    (net (code "79") (name "VCC5V") (class "Default")
      (node (ref "C10") (pin "1") (pinfunction "1_1") (pintype "passive"))
      (node (ref "C7") (pin "1") (pinfunction "1_1") (pintype "passive"))
      (node (ref "J1") (pin "VCC5V@1") (pinfunction "VCC-5V_VCC5V@1") (pintype "power_in"))
      (node (ref "SJ1") (pin "1") (pinfunction "1_1") (pintype "passive"))
      (node (ref "SJ3") (pin "3") (pinfunction "3_3") (pintype "passive"))
    )
    (net (code "80") (name "unconnected-(J1-PadAP-EINT1)") (class "Default")
      (node (ref "J1") (pin "AP-EINT1") (pinfunction "AP-EINT1_AP-EINT1") (pintype "passive"))
    )
    (net (code "81") (name "unconnected-(J1-PadCSID6)") (class "Default")
      (node (ref "J1") (pin "CSID6") (pinfunction "CSID6_CSID6") (pintype "passive"))
    )
    (net (code "82") (name "unconnected-(J1-PadCSID7)") (class "Default")
      (node (ref "J1") (pin "CSID7") (pinfunction "CSID7_CSID7") (pintype "passive"))
    )
    (net (code "83") (name "unconnected-(J1-PadMICIN1)") (class "Default")
      (node (ref "J1") (pin "MICIN1") (pinfunction "MICIN1_MICIN1") (pintype "passive"))
    )
    (net (code "84") (name "unconnected-(J1-PadMICM)") (class "Default")
      (node (ref "J1") (pin "MICM") (pinfunction "MICM_MICM") (pintype "passive"))
    )
    (net (code "85") (name "unconnected-(J1-PadTS)") (class "Default")
      (node (ref "J1") (pin "TS") (pinfunction "TS_TS") (pintype "passive"))
    )
    (net (code "86") (name "unconnected-(J1-PadXIO-P0)") (class "Default")
      (node (ref "J1") (pin "XIO-P0") (pinfunction "XIO-P0_XIO-P0") (pintype "passive"))
    )
    (net (code "87") (name "unconnected-(J1-PadXIO-P1)") (class "Default")
      (node (ref "J1") (pin "XIO-P1") (pinfunction "XIO-P1_XIO-P1") (pintype "passive"))
    )
    (net (code "88") (name "unconnected-(J2-PadD+)") (class "Default")
      (node (ref "J2") (pin "D+") (pinfunction "D+_D+") (pintype "bidirectional"))
    )
    (net (code "89") (name "unconnected-(J2-PadD-)") (class "Default")
      (node (ref "J2") (pin "D-") (pinfunction "D-_D-") (pintype "bidirectional"))
    )
    (net (code "90") (name "unconnected-(J2-USBID-PadID)") (class "Default")
      (node (ref "J2") (pin "ID") (pinfunction "USBID_ID") (pintype "bidirectional"))
    )
    (net (code "91") (name "unconnected-(U3-NC-Pad3)") (class "Default")
      (node (ref "U3") (pin "3") (pinfunction "NC_3") (pintype "bidirectional"))
    )
    (net (code "92") (name "unconnected-(U3-NC-Pad4)") (class "Default")
      (node (ref "U3") (pin "4") (pinfunction "NC_4") (pintype "bidirectional"))
    )
    (net (code "93") (name "unconnected-(U3-NC-Pad5)") (class "Default")
      (node (ref "U3") (pin "5") (pinfunction "NC_5") (pintype "bidirectional"))
    )
    (net (code "94") (name "unconnected-(U3-NC-Pad6)") (class "Default")
      (node (ref "U3") (pin "6") (pinfunction "NC_6") (pintype "bidirectional"))
    )
    (net (code "95") (name "unconnected-(X1AC-1-Pad35)") (class "Default")
      (node (ref "X1") (pin "35") (pinfunction "1_35") (pintype "passive"))
    )
  )
)
